# EEPROM.net
KiCad netlist of a schematic drawn in Altium Designer
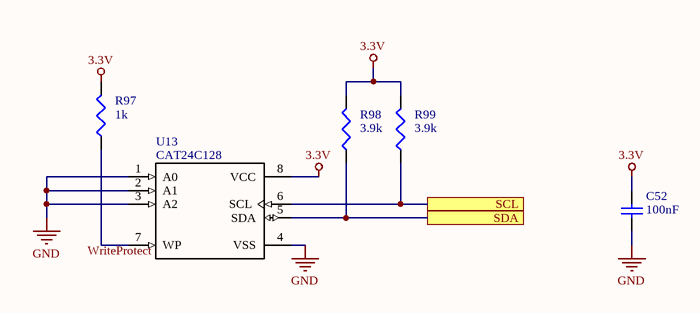
[diagram p0: EEPROM.SchDoc]

(export (version "E")
  (design (tool "Eeschema 10.0.6"))
  (components
    (comp (ref "C52")
      (value "100nF")
      (footprint "0603 to 0805 SMD")
      (fields (field (name "Comment") "Cap"))
      (libsource (lib "RC0805FR-0751K1L") (part "Cap"))
    )
    (comp (ref "R97")
      (value "1k")
      (footprint "0603 Footprint")
      (description "Resistor")
      (fields (field (name "Comment") "Res3") (field (name "PUBLISHER") "Altium Limited"))
      (libsource (lib "Miscellaneous Devices") (part "Res3"))
    )
    (comp (ref "R98")
      (value "3.9k")
      (footprint "0603 Footprint")
      (description "Resistor")
      (fields (field (name "Comment") "Res3") (field (name "PUBLISHER") "Altium Limited"))
      (libsource (lib "Miscellaneous Devices") (part "Res3"))
    )
    (comp (ref "R99")
      (value "3.9k")
      (footprint "0603 Footprint")
      (description "Resistor")
      (fields (field (name "Comment") "Res3") (field (name "PUBLISHER") "Altium Limited"))
      (libsource (lib "Miscellaneous Devices") (part "Res3"))
    )
    (comp (ref "U13")
      (value "CAT24C128")
      (footprint "EEPROM")
      (description "EEPROM Serial-I2C 128K-bit 16K x 8 2.5V/3.3V/5V 8-Pin UDFN EP T/R")
      (fields (field (name "MP") "CAT24C128HU4IGT3") (field (name "MF") "ON Semiconductor"))
      (libsource (lib "AvionicsParts") (part "CAT24C128HU4IGT3"))
    )
  )
  (nets
    (net (code "1") (name "/SCL") (class "Default")
      (node (ref "R99") (pin "1") (pinfunction "1_1") (pintype "passive"))
      (node (ref "U13") (pin "6") (pinfunction "SCL_6") (pintype "input"))
    )
    (net (code "2") (name "/SDA") (class "Default")
      (node (ref "R98") (pin "1") (pinfunction "1_1") (pintype "passive"))
      (node (ref "U13") (pin "5") (pinfunction "SDA_5") (pintype "bidirectional"))
    )
    (net (code "4") (name "3.3V") (class "Default")
      (node (ref "C52") (pin "2") (pinfunction "2_2") (pintype "passive"))
      (node (ref "R97") (pin "2") (pinfunction "2_2") (pintype "passive"))
      (node (ref "R98") (pin "2") (pinfunction "2_2") (pintype "passive"))
      (node (ref "R99") (pin "2") (pinfunction "2_2") (pintype "passive"))
      (node (ref "U13") (pin "8") (pinfunction "VCC_8") (pintype "power_in"))
    )
    (net (code "5") (name "GND") (class "Default")
      (node (ref "C52") (pin "1") (pinfunction "1_1") (pintype "passive"))
      (node (ref "U13") (pin "1") (pinfunction "A0_1") (pintype "input"))
      (node (ref "U13") (pin "2") (pinfunction "A1_2") (pintype "input"))
      (node (ref "U13") (pin "3") (pinfunction "A2_3") (pintype "input"))
      (node (ref "U13") (pin "4") (pinfunction "VSS_4") (pintype "power_in"))
    )
    (net (code "6") (name "Net-(U13-WP)") (class "Default")
      (node (ref "R97") (pin "1") (pinfunction "1_1") (pintype "passive"))
      (node (ref "U13") (pin "7") (pinfunction "WP_7") (pintype "input"))
    )
  )
)
